# 7segement4digits1badidea-many-digits-mk-.net
KiCad netlist of a schematic drawn in EAGLE
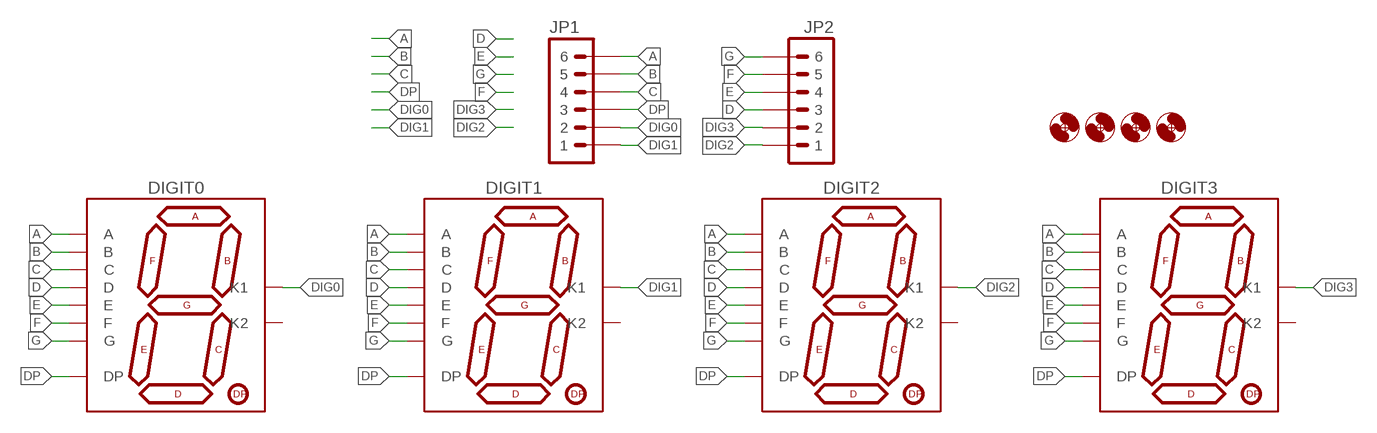
[diagram p0: schematic, sheet 1]

(export (version "E")
  (design (tool "Eeschema 10.0.6"))
  (components
    (comp (ref "DIGIT0")
      (value "7SEG_1DIGPTH-25.4MM")
      (footprint "eagle-import:7SEG_1DIG_25.4MM")
      (libsource (lib "eagle-import") (part "7SEG_1DIGPTH-25.4MM"))
    )
    (comp (ref "DIGIT1")
      (value "7SEG_1DIGPTH-25.4MM")
      (footprint "eagle-import:7SEG_1DIG_25.4MM")
      (libsource (lib "eagle-import") (part "7SEG_1DIGPTH-25.4MM"))
    )
    (comp (ref "DIGIT2")
      (value "7SEG_1DIGPTH-25.4MM")
      (footprint "eagle-import:7SEG_1DIG_25.4MM")
      (libsource (lib "eagle-import") (part "7SEG_1DIGPTH-25.4MM"))
    )
    (comp (ref "DIGIT3")
      (value "7SEG_1DIGPTH-25.4MM")
      (footprint "eagle-import:7SEG_1DIG_25.4MM")
      (libsource (lib "eagle-import") (part "7SEG_1DIGPTH-25.4MM"))
    )
    (comp (ref "H1")
      (value "HOLE#2")
      (footprint "eagle-import:HOLE-#2")
      (libsource (lib "eagle-import") (part "HOLE#2"))
    )
    (comp (ref "H2")
      (value "HOLE#2")
      (footprint "eagle-import:HOLE-#2")
      (libsource (lib "eagle-import") (part "HOLE#2"))
    )
    (comp (ref "H3")
      (value "HOLE#2")
      (footprint "eagle-import:HOLE-#2")
      (libsource (lib "eagle-import") (part "HOLE#2"))
    )
    (comp (ref "H4")
      (value "HOLE#2")
      (footprint "eagle-import:HOLE-#2")
      (libsource (lib "eagle-import") (part "HOLE#2"))
    )
    (comp (ref "JP1")
      (value "M06-NOBS-PTH")
      (footprint "eagle-import:1X06_NOLOCK_FUCKITALL")
      (libsource (lib "eagle-import") (part "M06-NOBS-PTH"))
    )
    (comp (ref "JP2")
      (value "M06-NOBS-PTH")
      (footprint "eagle-import:1X06_NOLOCK_FUCKITALL")
      (libsource (lib "eagle-import") (part "M06-NOBS-PTH"))
    )
  )
  (nets
    (net (code "1") (name "A") (class "Default")
      (node (ref "DIGIT0") (pin "7") (pinfunction "A_7") (pintype "bidirectional"))
      (node (ref "DIGIT1") (pin "7") (pinfunction "A_7") (pintype "bidirectional"))
      (node (ref "DIGIT2") (pin "7") (pinfunction "A_7") (pintype "bidirectional"))
      (node (ref "DIGIT3") (pin "7") (pinfunction "A_7") (pintype "bidirectional"))
      (node (ref "JP1") (pin "6") (pinfunction "6_6") (pintype "passive"))
    )
    (net (code "2") (name "B") (class "Default")
      (node (ref "DIGIT0") (pin "6") (pinfunction "B_6") (pintype "bidirectional"))
      (node (ref "DIGIT1") (pin "6") (pinfunction "B_6") (pintype "bidirectional"))
      (node (ref "DIGIT2") (pin "6") (pinfunction "B_6") (pintype "bidirectional"))
      (node (ref "DIGIT3") (pin "6") (pinfunction "B_6") (pintype "bidirectional"))
      (node (ref "JP1") (pin "5") (pinfunction "5_5") (pintype "passive"))
    )
    (net (code "3") (name "C") (class "Default")
      (node (ref "DIGIT0") (pin "4") (pinfunction "C_4") (pintype "bidirectional"))
      (node (ref "DIGIT1") (pin "4") (pinfunction "C_4") (pintype "bidirectional"))
      (node (ref "DIGIT2") (pin "4") (pinfunction "C_4") (pintype "bidirectional"))
      (node (ref "DIGIT3") (pin "4") (pinfunction "C_4") (pintype "bidirectional"))
      (node (ref "JP1") (pin "4") (pinfunction "4_4") (pintype "passive"))
    )
    (net (code "4") (name "D") (class "Default")
      (node (ref "DIGIT0") (pin "2") (pinfunction "D_2") (pintype "bidirectional"))
      (node (ref "DIGIT1") (pin "2") (pinfunction "D_2") (pintype "bidirectional"))
      (node (ref "DIGIT2") (pin "2") (pinfunction "D_2") (pintype "bidirectional"))
      (node (ref "DIGIT3") (pin "2") (pinfunction "D_2") (pintype "bidirectional"))
      (node (ref "JP2") (pin "3") (pinfunction "3_3") (pintype "passive"))
    )
    (net (code "5") (name "DIG0") (class "Default")
      (node (ref "DIGIT0") (pin "3") (pinfunction "K1_3") (pintype "bidirectional"))
      (node (ref "JP1") (pin "2") (pinfunction "2_2") (pintype "passive"))
    )
    (net (code "6") (name "DIG1") (class "Default")
      (node (ref "DIGIT1") (pin "3") (pinfunction "K1_3") (pintype "bidirectional"))
      (node (ref "JP1") (pin "1") (pinfunction "1_1") (pintype "passive"))
    )
    (net (code "7") (name "DIG2") (class "Default")
      (node (ref "DIGIT2") (pin "3") (pinfunction "K1_3") (pintype "bidirectional"))
      (node (ref "JP2") (pin "1") (pinfunction "1_1") (pintype "passive"))
    )
    (net (code "8") (name "DIG3") (class "Default")
      (node (ref "DIGIT3") (pin "3") (pinfunction "K1_3") (pintype "bidirectional"))
      (node (ref "JP2") (pin "2") (pinfunction "2_2") (pintype "passive"))
    )
    (net (code "9") (name "DP") (class "Default")
      (node (ref "DIGIT0") (pin "5") (pinfunction "DP_5") (pintype "bidirectional"))
      (node (ref "DIGIT1") (pin "5") (pinfunction "DP_5") (pintype "bidirectional"))
      (node (ref "DIGIT2") (pin "5") (pinfunction "DP_5") (pintype "bidirectional"))
      (node (ref "DIGIT3") (pin "5") (pinfunction "DP_5") (pintype "bidirectional"))
      (node (ref "JP1") (pin "3") (pinfunction "3_3") (pintype "passive"))
    )
    (net (code "10") (name "E") (class "Default")
      (node (ref "DIGIT0") (pin "1") (pinfunction "E_1") (pintype "bidirectional"))
      (node (ref "DIGIT1") (pin "1") (pinfunction "E_1") (pintype "bidirectional"))
      (node (ref "DIGIT2") (pin "1") (pinfunction "E_1") (pintype "bidirectional"))
      (node (ref "DIGIT3") (pin "1") (pinfunction "E_1") (pintype "bidirectional"))
      (node (ref "JP2") (pin "4") (pinfunction "4_4") (pintype "passive"))
    )
    (net (code "11") (name "F") (class "Default")
      (node (ref "DIGIT0") (pin "9") (pinfunction "F_9") (pintype "bidirectional"))
      (node (ref "DIGIT1") (pin "9") (pinfunction "F_9") (pintype "bidirectional"))
      (node (ref "DIGIT2") (pin "9") (pinfunction "F_9") (pintype "bidirectional"))
      (node (ref "DIGIT3") (pin "9") (pinfunction "F_9") (pintype "bidirectional"))
      (node (ref "JP2") (pin "5") (pinfunction "5_5") (pintype "passive"))
    )
    (net (code "12") (name "G") (class "Default")
      (node (ref "DIGIT0") (pin "10") (pinfunction "G_10") (pintype "bidirectional"))
      (node (ref "DIGIT1") (pin "10") (pinfunction "G_10") (pintype "bidirectional"))
      (node (ref "DIGIT2") (pin "10") (pinfunction "G_10") (pintype "bidirectional"))
      (node (ref "DIGIT3") (pin "10") (pinfunction "G_10") (pintype "bidirectional"))
      (node (ref "JP2") (pin "6") (pinfunction "6_6") (pintype "passive"))
    )
    (net (code "13") (name "unconnected-(DIGIT0-K2-Pad8)") (class "Default")
      (node (ref "DIGIT0") (pin "8") (pinfunction "K2_8") (pintype "bidirectional"))
    )
    (net (code "14") (name "unconnected-(DIGIT1-K2-Pad8)") (class "Default")
      (node (ref "DIGIT1") (pin "8") (pinfunction "K2_8") (pintype "bidirectional"))
    )
    (net (code "15") (name "unconnected-(DIGIT2-K2-Pad8)") (class "Default")
      (node (ref "DIGIT2") (pin "8") (pinfunction "K2_8") (pintype "bidirectional"))
    )
    (net (code "16") (name "unconnected-(DIGIT3-K2-Pad8)") (class "Default")
      (node (ref "DIGIT3") (pin "8") (pinfunction "K2_8") (pintype "bidirectional"))
    )
  )
)
